# Kilobot_Controller_IR.net
KiCad netlist of a schematic drawn in Altium Designer
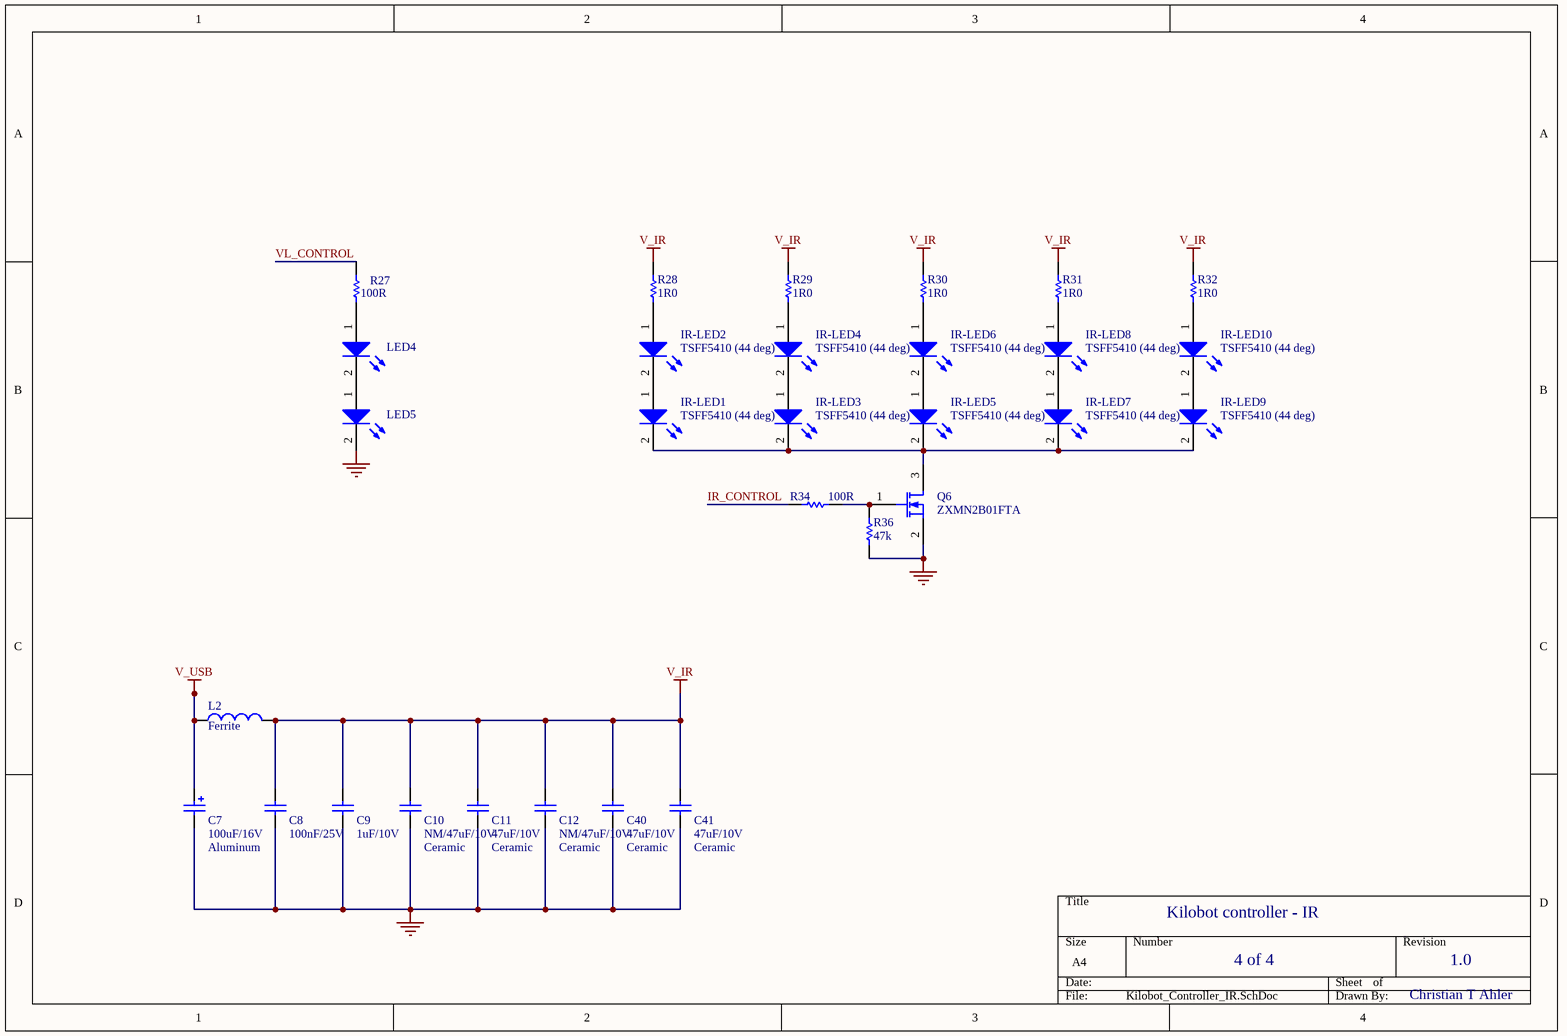
[diagram p0: Kilobot_Controller_IR.SchDoc]

(export (version "E")
  (design (tool "Eeschema 10.0.6"))
  (components
    (comp (ref "C7")
      (value "Aluminum")
      (footprint "cap5mm")
      (fields (field (name "ALTIUM_VALUE") "100uF/16V"))
      (libsource (lib "Kilobot_Controller") (part "CAP"))
    )
    (comp (ref "C8")
      (value "100nF/25V")
      (footprint "RESC1608L")
      (description "Ceramic Chip Capacitor - Standard")
      (fields (field (name "Comment") "C0603"))
      (libsource (lib "KEMET Chip Capacitor") (part "C0603"))
    )
    (comp (ref "C9")
      (value "1uF/10V")
      (footprint "RESC1608L")
      (description "Ceramic Chip Capacitor - Standard")
      (fields (field (name "Comment") "C0603"))
      (libsource (lib "KEMET Chip Capacitor") (part "C0603"))
    )
    (comp (ref "C10")
      (value "Ceramic")
      (footprint "8RB-1206")
      (fields (field (name "ALTIUM_VALUE") "NM/47uF/10V"))
      (libsource (lib "Kilobot_Controller") (part "CAP2220"))
    )
    (comp (ref "C11")
      (value "Ceramic")
      (footprint "8RB-1206")
      (fields (field (name "ALTIUM_VALUE") "47uF/10V"))
      (libsource (lib "Kilobot_Controller") (part "CAP2220"))
    )
    (comp (ref "C12")
      (value "Ceramic")
      (footprint "8RB-1206")
      (fields (field (name "ALTIUM_VALUE") "NM/47uF/10V"))
      (libsource (lib "Kilobot_Controller") (part "CAP2220"))
    )
    (comp (ref "C40")
      (value "Ceramic")
      (footprint "8RB-1206")
      (fields (field (name "ALTIUM_VALUE") "47uF/10V"))
      (libsource (lib "Kilobot_Controller") (part "CAP2220"))
    )
    (comp (ref "C41")
      (value "Ceramic")
      (footprint "8RB-1206")
      (fields (field (name "ALTIUM_VALUE") "47uF/10V"))
      (libsource (lib "Kilobot_Controller") (part "CAP2220"))
    )
    (comp (ref "IR-LED1")
      (value "TSFF5410 (44 deg)")
      (footprint "IR-LED")
      (fields (field (name "Comment") "IR-LED"))
      (libsource (lib "KilobotCommercial") (part "IR-LED"))
    )
    (comp (ref "IR-LED2")
      (value "TSFF5410 (44 deg)")
      (footprint "IR-LED")
      (fields (field (name "Comment") "IR-LED"))
      (libsource (lib "KilobotCommercial") (part "IR-LED"))
    )
    (comp (ref "IR-LED3")
      (value "TSFF5410 (44 deg)")
      (footprint "IR-LED")
      (fields (field (name "Comment") "IR-LED"))
      (libsource (lib "KilobotCommercial") (part "IR-LED"))
    )
    (comp (ref "IR-LED4")
      (value "TSFF5410 (44 deg)")
      (footprint "IR-LED")
      (fields (field (name "Comment") "IR-LED"))
      (libsource (lib "KilobotCommercial") (part "IR-LED"))
    )
    (comp (ref "IR-LED5")
      (value "TSFF5410 (44 deg)")
      (footprint "IR-LED")
      (fields (field (name "Comment") "IR-LED"))
      (libsource (lib "KilobotCommercial") (part "IR-LED"))
    )
    (comp (ref "IR-LED6")
      (value "TSFF5410 (44 deg)")
      (footprint "IR-LED")
      (fields (field (name "Comment") "IR-LED"))
      (libsource (lib "KilobotCommercial") (part "IR-LED"))
    )
    (comp (ref "IR-LED7")
      (value "TSFF5410 (44 deg)")
      (footprint "IR-LED")
      (fields (field (name "Comment") "IR-LED"))
      (libsource (lib "KilobotCommercial") (part "IR-LED"))
    )
    (comp (ref "IR-LED8")
      (value "TSFF5410 (44 deg)")
      (footprint "IR-LED")
      (fields (field (name "Comment") "IR-LED"))
      (libsource (lib "KilobotCommercial") (part "IR-LED"))
    )
    (comp (ref "IR-LED9")
      (value "TSFF5410 (44 deg)")
      (footprint "IR-LED")
      (fields (field (name "Comment") "IR-LED"))
      (libsource (lib "KilobotCommercial") (part "IR-LED"))
    )
    (comp (ref "IR-LED10")
      (value "TSFF5410 (44 deg)")
      (footprint "IR-LED")
      (fields (field (name "Comment") "IR-LED"))
      (libsource (lib "KilobotCommercial") (part "IR-LED"))
    )
    (comp (ref "L2")
      (value "Ferrite")
      (footprint "RESC2012N")
      (description "Inductor")
      (libsource (lib "Miscellaneous Devices") (part "Inductor"))
    )
    (comp (ref "LED4") (value "LED") (footprint "LED0603") (libsource (lib "KilobotCommercial") (part "LED")))
    (comp (ref "LED5") (value "LED") (footprint "LED0603") (libsource (lib "KilobotCommercial") (part "LED")))
    (comp (ref "Q6")
      (value "ZXMN2B01FTA")
      (footprint "sot23-3")
      (fields (field (name "Comment") "NMOS23"))
      (libsource (lib "KilobotCommercial") (part "NMOS23"))
    )
    (comp (ref "R27")
      (value "100R")
      (footprint "RESC1608L")
      (description "Resistor")
      (fields (field (name "Comment") "Res1"))
      (libsource (lib "Miscellaneous Devices") (part "Res1"))
    )
    (comp (ref "R28")
      (value "1R0")
      (footprint "RESC2012L")
      (description "Resistor")
      (fields (field (name "Comment") "Res1"))
      (libsource (lib "Miscellaneous Devices") (part "Res1"))
    )
    (comp (ref "R29")
      (value "1R0")
      (footprint "RESC2012L")
      (description "Resistor")
      (fields (field (name "Comment") "Res1"))
      (libsource (lib "Miscellaneous Devices") (part "Res1"))
    )
    (comp (ref "R30")
      (value "1R0")
      (footprint "RESC2012L")
      (description "Resistor")
      (fields (field (name "Comment") "Res1"))
      (libsource (lib "Miscellaneous Devices") (part "Res1"))
    )
    (comp (ref "R31")
      (value "1R0")
      (footprint "RESC2012L")
      (description "Resistor")
      (fields (field (name "Comment") "Res1"))
      (libsource (lib "Miscellaneous Devices") (part "Res1"))
    )
    (comp (ref "R32")
      (value "1R0")
      (footprint "RESC2012L")
      (description "Resistor")
      (fields (field (name "Comment") "Res1"))
      (libsource (lib "Miscellaneous Devices") (part "Res1"))
    )
    (comp (ref "R34")
      (value "100R")
      (footprint "RESC1608L")
      (description "Resistor")
      (fields (field (name "Comment") "Res1"))
      (libsource (lib "Miscellaneous Devices") (part "Res1"))
    )
    (comp (ref "R36")
      (value "47k")
      (footprint "RESC1608L")
      (description "Resistor")
      (fields (field (name "Comment") "Res1"))
      (libsource (lib "Miscellaneous Devices") (part "Res1"))
    )
  )
  (nets
    (net (code "1") (name "/IR_CONTROL") (class "Default")
      (node (ref "R34") (pin "2") (pinfunction "2_2") (pintype "passive"))
    )
    (net (code "2") (name "/VL_CONTROL") (class "Default")
      (node (ref "R27") (pin "2") (pinfunction "2_2") (pintype "passive"))
    )
    (net (code "3") (name "GND") (class "Default")
      (node (ref "C10") (pin "1") (pinfunction "1_1") (pintype "passive"))
      (node (ref "C11") (pin "1") (pinfunction "1_1") (pintype "passive"))
      (node (ref "C12") (pin "1") (pinfunction "1_1") (pintype "passive"))
      (node (ref "C40") (pin "1") (pinfunction "1_1") (pintype "passive"))
      (node (ref "C41") (pin "1") (pinfunction "1_1") (pintype "passive"))
      (node (ref "C7") (pin "2") (pinfunction "2_2") (pintype "passive"))
      (node (ref "C8") (pin "2") (pinfunction "2_2") (pintype "passive"))
      (node (ref "C9") (pin "1") (pinfunction "1_1") (pintype "passive"))
      (node (ref "LED5") (pin "2") (pinfunction "K_2") (pintype "passive"))
      (node (ref "Q6") (pin "2") (pinfunction "S_2") (pintype "passive"))
      (node (ref "R36") (pin "1") (pinfunction "1_1") (pintype "passive"))
    )
    (net (code "4") (name "Net-(IR-LED1-A)") (class "Default")
      (node (ref "IR-LED1") (pin "1") (pinfunction "A_1") (pintype "passive"))
      (node (ref "IR-LED2") (pin "2") (pinfunction "K_2") (pintype "passive"))
    )
    (net (code "5") (name "Net-(IR-LED1-K)") (class "Default")
      (node (ref "IR-LED1") (pin "2") (pinfunction "K_2") (pintype "passive"))
      (node (ref "IR-LED3") (pin "2") (pinfunction "K_2") (pintype "passive"))
      (node (ref "IR-LED5") (pin "2") (pinfunction "K_2") (pintype "passive"))
      (node (ref "IR-LED7") (pin "2") (pinfunction "K_2") (pintype "passive"))
      (node (ref "IR-LED9") (pin "2") (pinfunction "K_2") (pintype "passive"))
      (node (ref "Q6") (pin "3") (pinfunction "D_3") (pintype "passive"))
    )
    (net (code "6") (name "Net-(IR-LED2-A)") (class "Default")
      (node (ref "IR-LED2") (pin "1") (pinfunction "A_1") (pintype "passive"))
      (node (ref "R28") (pin "1") (pinfunction "1_1") (pintype "passive"))
    )
    (net (code "7") (name "Net-(IR-LED3-A)") (class "Default")
      (node (ref "IR-LED3") (pin "1") (pinfunction "A_1") (pintype "passive"))
      (node (ref "IR-LED4") (pin "2") (pinfunction "K_2") (pintype "passive"))
    )
    (net (code "8") (name "Net-(IR-LED4-A)") (class "Default")
      (node (ref "IR-LED4") (pin "1") (pinfunction "A_1") (pintype "passive"))
      (node (ref "R29") (pin "1") (pinfunction "1_1") (pintype "passive"))
    )
    (net (code "9") (name "Net-(IR-LED5-A)") (class "Default")
      (node (ref "IR-LED5") (pin "1") (pinfunction "A_1") (pintype "passive"))
      (node (ref "IR-LED6") (pin "2") (pinfunction "K_2") (pintype "passive"))
    )
    (net (code "10") (name "Net-(IR-LED6-A)") (class "Default")
      (node (ref "IR-LED6") (pin "1") (pinfunction "A_1") (pintype "passive"))
      (node (ref "R30") (pin "1") (pinfunction "1_1") (pintype "passive"))
    )
    (net (code "11") (name "Net-(IR-LED7-A)") (class "Default")
      (node (ref "IR-LED7") (pin "1") (pinfunction "A_1") (pintype "passive"))
      (node (ref "IR-LED8") (pin "2") (pinfunction "K_2") (pintype "passive"))
    )
    (net (code "12") (name "Net-(IR-LED8-A)") (class "Default")
      (node (ref "IR-LED8") (pin "1") (pinfunction "A_1") (pintype "passive"))
      (node (ref "R31") (pin "1") (pinfunction "1_1") (pintype "passive"))
    )
    (net (code "13") (name "Net-(IR-LED10-A)") (class "Default")
      (node (ref "IR-LED10") (pin "1") (pinfunction "A_1") (pintype "passive"))
      (node (ref "R32") (pin "1") (pinfunction "1_1") (pintype "passive"))
    )
    (net (code "14") (name "Net-(IR-LED10-K)") (class "Default")
      (node (ref "IR-LED10") (pin "2") (pinfunction "K_2") (pintype "passive"))
      (node (ref "IR-LED9") (pin "1") (pinfunction "A_1") (pintype "passive"))
    )
    (net (code "15") (name "Net-(LED4-A)") (class "Default")
      (node (ref "LED4") (pin "1") (pinfunction "A_1") (pintype "passive"))
      (node (ref "R27") (pin "1") (pinfunction "1_1") (pintype "passive"))
    )
    (net (code "16") (name "Net-(LED4-K)") (class "Default")
      (node (ref "LED4") (pin "2") (pinfunction "K_2") (pintype "passive"))
      (node (ref "LED5") (pin "1") (pinfunction "A_1") (pintype "passive"))
    )
    (net (code "17") (name "Net-(Q6-G)") (class "Default")
      (node (ref "Q6") (pin "1") (pinfunction "G_1") (pintype "passive"))
      (node (ref "R34") (pin "1") (pinfunction "1_1") (pintype "passive"))
      (node (ref "R36") (pin "2") (pinfunction "2_2") (pintype "passive"))
    )
    (net (code "18") (name "V_IR") (class "Default")
      (node (ref "C10") (pin "2") (pinfunction "2_2") (pintype "passive"))
      (node (ref "C11") (pin "2") (pinfunction "2_2") (pintype "passive"))
      (node (ref "C12") (pin "2") (pinfunction "2_2") (pintype "passive"))
      (node (ref "C40") (pin "2") (pinfunction "2_2") (pintype "passive"))
      (node (ref "C41") (pin "2") (pinfunction "2_2") (pintype "passive"))
      (node (ref "C8") (pin "1") (pinfunction "1_1") (pintype "passive"))
      (node (ref "C9") (pin "2") (pinfunction "2_2") (pintype "passive"))
      (node (ref "L2") (pin "2") (pinfunction "2_2") (pintype "passive"))
      (node (ref "R28") (pin "2") (pinfunction "2_2") (pintype "passive"))
      (node (ref "R29") (pin "2") (pinfunction "2_2") (pintype "passive"))
      (node (ref "R30") (pin "2") (pinfunction "2_2") (pintype "passive"))
      (node (ref "R31") (pin "2") (pinfunction "2_2") (pintype "passive"))
      (node (ref "R32") (pin "2") (pinfunction "2_2") (pintype "passive"))
    )
    (net (code "19") (name "V_USB") (class "Default")
      (node (ref "C7") (pin "1") (pinfunction "1_1") (pintype "passive"))
      (node (ref "L2") (pin "1") (pinfunction "1_1") (pintype "passive"))
    )
  )
)
